# -V4_1.net
KiCad netlist of a schematic drawn in Altium Designer
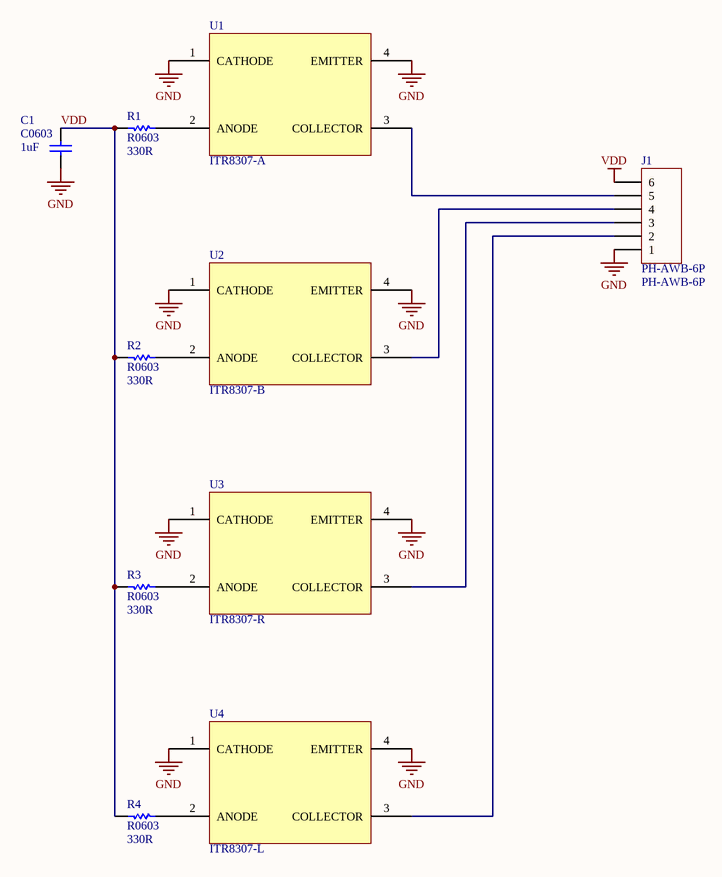
[diagram p0: 头部位置编码器-V4.1.SchDoc]

(export (version "E")
  (design (tool "Eeschema 10.0.6"))
  (components
    (comp (ref "C1")
      (value "C0603")
      (footprint "C0603_M1608")
      (description "Capacitor")
      (fields (field (name "ALTIUM_VALUE") "1uF") (field (name "PUBLISHER") "Altium Limited"))
      (libsource (lib "Miscellaneous Devices") (part "Cap"))
    )
    (comp (ref "J1")
      (value "PH-AWB-6P")
      (footprint "PH-AWB-6P")
      (description "Header, 6-Pin")
      (fields (field (name "ALTIUM_VALUE") "PH-AWB-6P") (field (name "PUBLISHER") "Altium Limited"))
      (libsource (lib "SCH") (part "PH2.0-6P"))
    )
    (comp (ref "R1")
      (value "R0603")
      (description "Resistor")
      (fields (field (name "ALTIUM_VALUE") "330R") (field (name "PUBLISHER") "Altium Limited"))
      (libsource (lib "Miscellaneous Devices") (part "Res1"))
    )
    (comp (ref "R2")
      (value "R0603")
      (description "Resistor")
      (fields (field (name "ALTIUM_VALUE") "330R") (field (name "PUBLISHER") "Altium Limited"))
      (libsource (lib "Miscellaneous Devices") (part "Res1"))
    )
    (comp (ref "R3")
      (value "R0603")
      (description "Resistor")
      (fields (field (name "ALTIUM_VALUE") "330R") (field (name "PUBLISHER") "Altium Limited"))
      (libsource (lib "Miscellaneous Devices") (part "Res1"))
    )
    (comp (ref "R4")
      (value "R0603")
      (description "Resistor")
      (fields (field (name "ALTIUM_VALUE") "330R") (field (name "PUBLISHER") "Altium Limited"))
      (libsource (lib "Miscellaneous Devices") (part "Res1"))
    )
    (comp (ref "U1") (value "ITR8307-A") (footprint "ITR8307") (libsource (lib "光电管") (part "Component_1")))
    (comp (ref "U2") (value "ITR8307-B") (footprint "ITR8307") (libsource (lib "光电管") (part "Component_1")))
    (comp (ref "U3") (value "ITR8307-R") (footprint "ITR8307") (libsource (lib "光电管") (part "Component_1")))
    (comp (ref "U4") (value "ITR8307-L") (footprint "ITR8307") (libsource (lib "光电管") (part "Component_1")))
  )
  (nets
    (net (code "1") (name "GND") (class "Default")
      (node (ref "C1") (pin "2") (pinfunction "2_2") (pintype "passive"))
      (node (ref "J1") (pin "1") (pinfunction "1_1") (pintype "passive"))
      (node (ref "U1") (pin "1") (pinfunction "CATHODE_1") (pintype "passive"))
      (node (ref "U1") (pin "4") (pinfunction "EMITTER_4") (pintype "passive"))
      (node (ref "U2") (pin "1") (pinfunction "CATHODE_1") (pintype "passive"))
      (node (ref "U2") (pin "4") (pinfunction "EMITTER_4") (pintype "passive"))
      (node (ref "U3") (pin "1") (pinfunction "CATHODE_1") (pintype "passive"))
      (node (ref "U3") (pin "4") (pinfunction "EMITTER_4") (pintype "passive"))
      (node (ref "U4") (pin "1") (pinfunction "CATHODE_1") (pintype "passive"))
      (node (ref "U4") (pin "4") (pinfunction "EMITTER_4") (pintype "passive"))
    )
    (net (code "2") (name "Net-(U1-ANODE)") (class "Default")
      (node (ref "R1") (pin "1") (pinfunction "1_1") (pintype "passive"))
      (node (ref "U1") (pin "2") (pinfunction "ANODE_2") (pintype "passive"))
    )
    (net (code "3") (name "Net-(U1-COLLECTOR)") (class "Default")
      (node (ref "J1") (pin "5") (pinfunction "5_5") (pintype "passive"))
      (node (ref "U1") (pin "3") (pinfunction "COLLECTOR_3") (pintype "passive"))
    )
    (net (code "4") (name "Net-(U2-ANODE)") (class "Default")
      (node (ref "R2") (pin "1") (pinfunction "1_1") (pintype "passive"))
      (node (ref "U2") (pin "2") (pinfunction "ANODE_2") (pintype "passive"))
    )
    (net (code "5") (name "Net-(U2-COLLECTOR)") (class "Default")
      (node (ref "J1") (pin "4") (pinfunction "4_4") (pintype "passive"))
      (node (ref "U2") (pin "3") (pinfunction "COLLECTOR_3") (pintype "passive"))
    )
    (net (code "6") (name "Net-(U3-ANODE)") (class "Default")
      (node (ref "R3") (pin "1") (pinfunction "1_1") (pintype "passive"))
      (node (ref "U3") (pin "2") (pinfunction "ANODE_2") (pintype "passive"))
    )
    (net (code "7") (name "Net-(U3-COLLECTOR)") (class "Default")
      (node (ref "J1") (pin "3") (pinfunction "3_3") (pintype "passive"))
      (node (ref "U3") (pin "3") (pinfunction "COLLECTOR_3") (pintype "passive"))
    )
    (net (code "8") (name "Net-(U4-ANODE)") (class "Default")
      (node (ref "R4") (pin "1") (pinfunction "1_1") (pintype "passive"))
      (node (ref "U4") (pin "2") (pinfunction "ANODE_2") (pintype "passive"))
    )
    (net (code "9") (name "Net-(U4-COLLECTOR)") (class "Default")
      (node (ref "J1") (pin "2") (pinfunction "2_2") (pintype "passive"))
      (node (ref "U4") (pin "3") (pinfunction "COLLECTOR_3") (pintype "passive"))
    )
    (net (code "10") (name "VDD") (class "Default")
      (node (ref "C1") (pin "1") (pinfunction "1_1") (pintype "passive"))
      (node (ref "J1") (pin "6") (pinfunction "6_6") (pintype "passive"))
      (node (ref "R1") (pin "2") (pinfunction "2_2") (pintype "passive"))
      (node (ref "R2") (pin "2") (pinfunction "2_2") (pintype "passive"))
      (node (ref "R3") (pin "2") (pinfunction "2_2") (pintype "passive"))
      (node (ref "R4") (pin "2") (pinfunction "2_2") (pintype "passive"))
    )
  )
)
